# ICM.net
KiCad netlist of a schematic drawn in Altium Designer
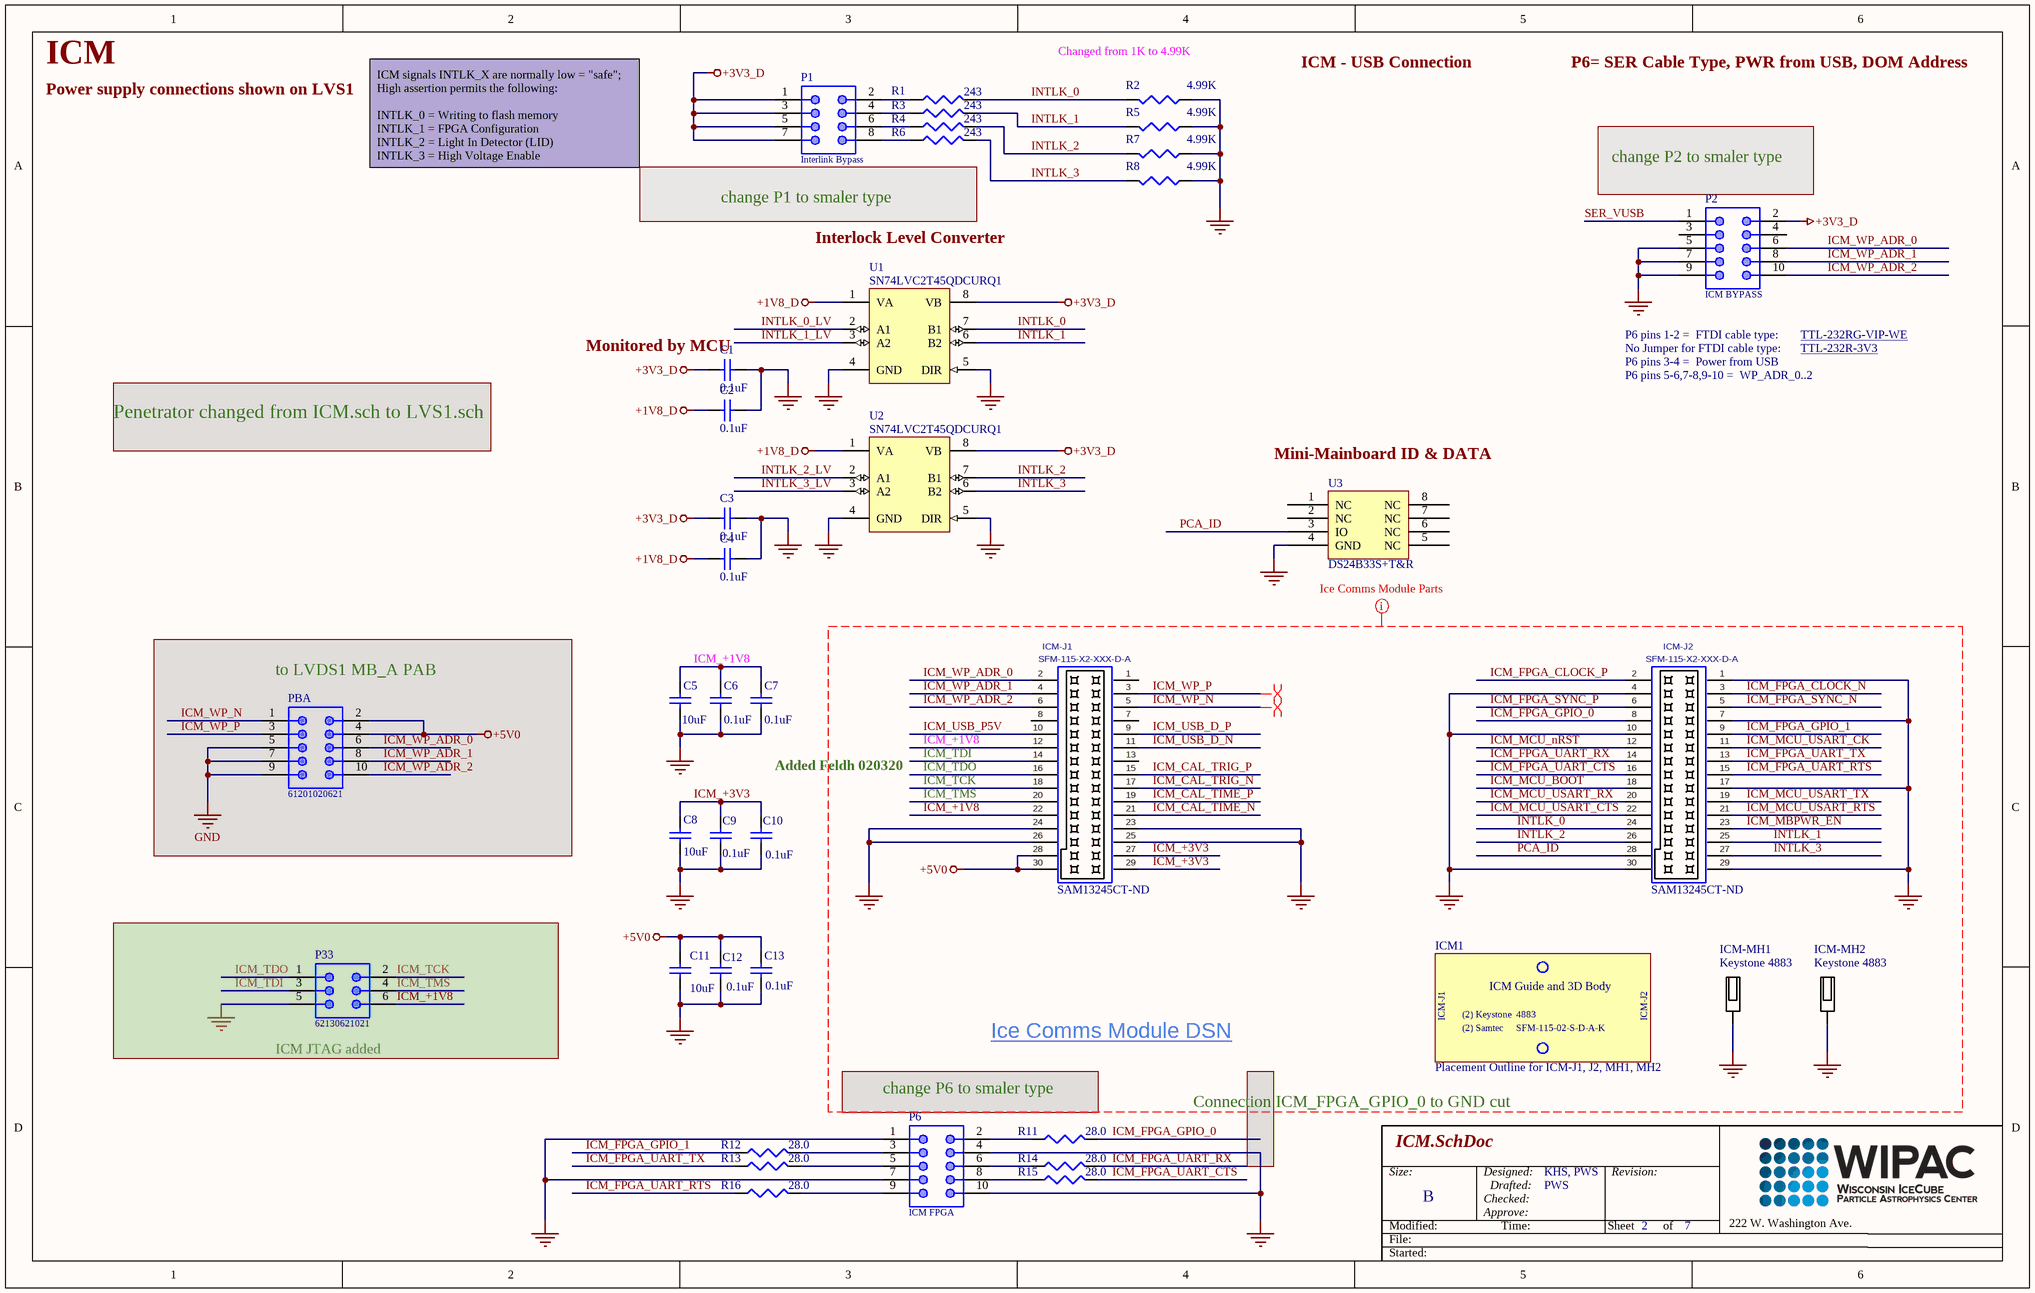
[diagram p0: ICM.SchDoc]

(export (version "E")
  (design (tool "Eeschema 10.0.6"))
  (components
    (comp (ref "C1")
      (value "0.1uF_603_50V")
      (footprint "CAPC_0603")
      (description "0.1µF ±10% 50V Ceramic Capacitor X7R 0603 (1608 Metric)")
      (fields
        (field (name "MANUFACTURER") "TDK")
        (field (name "MANUFACTURER PART NUMBER") "CGJ3E2X7R1H104K080AA")
        (field (name "CAPACITANCE") "0.1uF")
      )
      (libsource (lib "Custom1") (part "CapC_0.1uF_603_50V"))
    )
    (comp (ref "C2")
      (value "0.1uF_603_50V")
      (footprint "CAPC_0603")
      (description "0.1µF ±10% 50V Ceramic Capacitor X7R 0603 (1608 Metric)")
      (fields
        (field (name "MANUFACTURER") "TDK")
        (field (name "MANUFACTURER PART NUMBER") "CGJ3E2X7R1H104K080AA")
        (field (name "CAPACITANCE") "0.1uF")
      )
      (libsource (lib "Custom1") (part "CapC_0.1uF_603_50V"))
    )
    (comp (ref "C3")
      (value "0.1uF_603_50V")
      (footprint "CAPC_0603")
      (description "0.1µF ±10% 50V Ceramic Capacitor X7R 0603 (1608 Metric)")
      (fields
        (field (name "MANUFACTURER") "TDK")
        (field (name "MANUFACTURER PART NUMBER") "CGJ3E2X7R1H104K080AA")
        (field (name "CAPACITANCE") "0.1uF")
      )
      (libsource (lib "Custom1") (part "CapC_0.1uF_603_50V"))
    )
    (comp (ref "C4")
      (value "0.1uF_603_50V")
      (footprint "CAPC_0603")
      (description "0.1µF ±10% 50V Ceramic Capacitor X7R 0603 (1608 Metric)")
      (fields
        (field (name "MANUFACTURER") "TDK")
        (field (name "MANUFACTURER PART NUMBER") "CGJ3E2X7R1H104K080AA")
        (field (name "CAPACITANCE") "0.1uF")
      )
      (libsource (lib "Custom1") (part "CapC_0.1uF_603_50V"))
    )
    (comp (ref "C5")
      (value "10uF_805_10V")
      (footprint "CAPC_0805")
      (description "Capacitor")
      (fields
        (field (name "MANUFACTURER") "Murata")
        (field (name "MANUFACTURER PART NUMBER") "GCJ21BR71A106KE01L")
        (field (name "CAPACITANCE") "10uF")
      )
      (libsource (lib "Custom1") (part "CapC_10uF_805_10V"))
    )
    (comp (ref "C6")
      (value "0.1uF_603_50V")
      (footprint "CAPC_0603")
      (description "0.1µF ±10% 50V Ceramic Capacitor X7R 0603 (1608 Metric)")
      (fields
        (field (name "MANUFACTURER") "Murata")
        (field (name "MANUFACTURER PART NUMBER") "GCJ188R71H104KA12D")
        (field (name "CAPACITANCE") "0.1uF")
      )
      (libsource (lib "Custom1") (part "CapC_0.1uF_603_50V_GCJ"))
    )
    (comp (ref "C7")
      (value "0.1uF_603_50V")
      (footprint "CAPC_0603")
      (description "0.1µF ±10% 50V Ceramic Capacitor X7R 0603 (1608 Metric)")
      (fields
        (field (name "MANUFACTURER") "Murata")
        (field (name "MANUFACTURER PART NUMBER") "GCJ188R71H104KA12D")
        (field (name "CAPACITANCE") "0.1uF")
      )
      (libsource (lib "Custom1") (part "CapC_0.1uF_603_50V_GCJ"))
    )
    (comp (ref "C8")
      (value "10uF_805_10V")
      (footprint "CAPC_0805")
      (description "Capacitor")
      (fields
        (field (name "MANUFACTURER") "Murata")
        (field (name "MANUFACTURER PART NUMBER") "GCJ21BR71A106KE01L")
        (field (name "CAPACITANCE") "10uF")
      )
      (libsource (lib "Custom1") (part "CapC_10uF_805_10V"))
    )
    (comp (ref "C9")
      (value "0.1uF_603_50V")
      (footprint "CAPC_0603")
      (description "0.1µF ±10% 50V Ceramic Capacitor X7R 0603 (1608 Metric)")
      (fields
        (field (name "MANUFACTURER") "Murata")
        (field (name "MANUFACTURER PART NUMBER") "GCJ188R71H104KA12D")
        (field (name "CAPACITANCE") "0.1uF")
      )
      (libsource (lib "Custom1") (part "CapC_0.1uF_603_50V_GCJ"))
    )
    (comp (ref "C10")
      (value "0.1uF_603_50V")
      (footprint "CAPC_0603")
      (description "0.1µF ±10% 50V Ceramic Capacitor X7R 0603 (1608 Metric)")
      (fields
        (field (name "MANUFACTURER") "Murata")
        (field (name "MANUFACTURER PART NUMBER") "GCJ188R71H104KA12D")
        (field (name "CAPACITANCE") "0.1uF")
      )
      (libsource (lib "Custom1") (part "CapC_0.1uF_603_50V_GCJ"))
    )
    (comp (ref "C11")
      (value "10uF_805_10V")
      (footprint "CAPC_0805")
      (description "Capacitor")
      (fields
        (field (name "MANUFACTURER") "Murata")
        (field (name "MANUFACTURER PART NUMBER") "GCJ21BR71A106KE01L")
        (field (name "CAPACITANCE") "10uF")
      )
      (libsource (lib "Custom1") (part "CapC_10uF_805_10V"))
    )
    (comp (ref "C12")
      (value "0.1uF_603_50V")
      (footprint "CAPC_0603")
      (description "0.1µF ±10% 50V Ceramic Capacitor X7R 0603 (1608 Metric)")
      (fields
        (field (name "MANUFACTURER") "Murata")
        (field (name "MANUFACTURER PART NUMBER") "GCJ188R71H104KA12D")
        (field (name "CAPACITANCE") "0.1uF")
      )
      (libsource (lib "Custom1") (part "CapC_0.1uF_603_50V_GCJ"))
    )
    (comp (ref "C13")
      (value "0.1uF_603_50V")
      (footprint "CAPC_0603")
      (description "0.1µF ±10% 50V Ceramic Capacitor X7R 0603 (1608 Metric)")
      (fields
        (field (name "MANUFACTURER") "Murata")
        (field (name "MANUFACTURER PART NUMBER") "GCJ188R71H104KA12D")
        (field (name "CAPACITANCE") "0.1uF")
      )
      (libsource (lib "Custom1") (part "CapC_0.1uF_603_50V_GCJ"))
    )
    (comp (ref "ICM-J1")
      (value "SFM-115-X2-XXX-D-A")
      (footprint "SFM-115-X2-XXX-D-A")
      (description "SOCKET STRIP, .050\" (1.27mm) PITCH, SURFACE MOUNT.")
      (fields
        (field (name "MANUFACTURER") "Samtec")
        (field (name "MANUFACTURER PART NUMBER") "SFM-115-02-S-D-A-K-TR")
        (field (name "SUPPLIER PART NUMBER 1") "SAM13245CT-ND")
      )
      (libsource (lib "Custom1") (part "SFM-115-X2-XXX-D-A"))
    )
    (comp (ref "ICM-J2")
      (value "SFM-115-X2-XXX-D-A")
      (footprint "SFM-115-X2-XXX-D-A")
      (description "SOCKET STRIP, .050\" (1.27mm) PITCH, SURFACE MOUNT.")
      (fields
        (field (name "MANUFACTURER") "Samtec")
        (field (name "MANUFACTURER PART NUMBER") "SFM-115-02-S-D-A-K-TR")
        (field (name "SUPPLIER PART NUMBER 1") "SAM13245CT-ND")
      )
      (libsource (lib "Custom1") (part "SFM-115-X2-XXX-D-A"))
    )
    (comp (ref "ICM-MH1")
      (value "Keystone 4883")
      (footprint "Keystone 4883 solder")
      (description "standoff, SMT, 4-40, 0.25\" Long")
      (fields
        (field (name "MANUFACTURER") "Keystone Electronics")
        (field (name "MANUFACTURER PART NUMBER") "4883")
      )
      (libsource (lib "Custom1") (part "Keystone 4883"))
    )
    (comp (ref "ICM-MH2")
      (value "Keystone 4883")
      (footprint "Keystone 4883 solder")
      (description "standoff, SMT, 4-40, 0.25\" Long")
      (fields
        (field (name "MANUFACTURER") "Keystone Electronics")
        (field (name "MANUFACTURER PART NUMBER") "4883")
      )
      (libsource (lib "Custom1") (part "Keystone 4883"))
    )
    (comp (ref "ICM1")
      (value "Placement Outline for ICM-J1, J2, MH1, MH2")
      (footprint "Ice Comms Module")
      (libsource (lib "Custom1") (part "Ice Comms Module"))
    )
    (comp (ref "P1")
      (value "Interlink Bypass")
      (footprint "62100821021")
      (description "WR-PHD Pin Header, SMT, pitch 1.27mm, Dual Row, Vertical, 8pin")
      (fields (field (name "PART NUMBER") "62100821021") (field (name "PUBLISHER") "Wurth Elektronik"))
      (libsource (lib "WR-PHD") (part "62100821021"))
    )
    (comp (ref "P2")
      (value "ICM BYPASS")
      (footprint "62101021021")
      (description "WR-PHD Pin Header, SMT, pitch 1.27mm, Dual Row, Vertical, 10pin")
      (fields (field (name "PART NUMBER") "62101021021") (field (name "PUBLISHER") "Wurth Elektronik"))
      (libsource (lib "WR-PHD") (part "62101021021"))
    )
    (comp (ref "P6")
      (value "ICM FPGA")
      (footprint "62101021021")
      (description "WR-PHD Pin Header, SMT, pitch 1.27mm, Dual Row, Vertical, 10pin")
      (fields (field (name "PART NUMBER") "62101021021") (field (name "PUBLISHER") "Wurth Elektronik"))
      (libsource (lib "WR-PHD") (part "62101021021"))
    )
    (comp (ref "P33")
      (value "62130621021")
      (footprint "62130621021")
      (description "WR-PHD Pin Header, SMT, pitch 1.27mm, Dual Row, Vertical, 6pin")
      (fields (field (name "PUBLISHER") "Wurth Elektronik"))
      (libsource (lib "WR-PHD") (part "62130621021"))
    )
    (comp (ref "PBA")
      (value "61201020621")
      (footprint "61201020621")
      (description "Male Box Header WR-BHD, SMT, Vertical, pitch 2.54 mm, 10 pins")
      (fields (field (name "PUBLISHER") "Wurth Elektronik"))
      (libsource (lib "o162711v243 Altium_WR-BHD (rev19a)") (part "61201020621"))
    )
    (comp (ref "R1")
      (value "R_243_603_1%")
      (footprint "RES_0603")
      (description "RES 243 OHM 1/10W 1% 0603 SMD")
      (fields
        (field (name "MANUFACTURER") "Panasonic")
        (field (name "MANUFACTURER PART NUMBER") "ERJ3EKF2430V")
        (field (name "RESISTANCE") "243")
      )
      (libsource (lib "Custom1") (part "R_243_603_1%"))
    )
    (comp (ref "R2")
      (value "R_4.99K_603_1%")
      (footprint "RES_0603")
      (description "RES 4.99K OHM 1/10W 1% 0603 SMD")
      (fields
        (field (name "MANUFACTURER") "Panasonic")
        (field (name "MANUFACTURER PART NUMBER") "ERJ3EKF4991V")
        (field (name "RESISTANCE") "4.99K")
      )
      (libsource (lib "Custom1") (part "R_4.99K_603_1%"))
    )
    (comp (ref "R3")
      (value "R_243_603_1%")
      (footprint "RES_0603")
      (description "RES 243 OHM 1/10W 1% 0603 SMD")
      (fields
        (field (name "MANUFACTURER") "Panasonic")
        (field (name "MANUFACTURER PART NUMBER") "ERJ3EKF2430V")
        (field (name "RESISTANCE") "243")
      )
      (libsource (lib "Custom1") (part "R_243_603_1%"))
    )
    (comp (ref "R4")
      (value "R_243_603_1%")
      (footprint "RES_0603")
      (description "RES 243 OHM 1/10W 1% 0603 SMD")
      (fields
        (field (name "MANUFACTURER") "Panasonic")
        (field (name "MANUFACTURER PART NUMBER") "ERJ3EKF2430V")
        (field (name "RESISTANCE") "243")
      )
      (libsource (lib "Custom1") (part "R_243_603_1%"))
    )
    (comp (ref "R5")
      (value "R_4.99K_603_1%")
      (footprint "RES_0603")
      (description "RES 4.99K OHM 1/10W 1% 0603 SMD")
      (fields
        (field (name "MANUFACTURER") "Panasonic")
        (field (name "MANUFACTURER PART NUMBER") "ERJ3EKF4991V")
        (field (name "RESISTANCE") "4.99K")
      )
      (libsource (lib "Custom1") (part "R_4.99K_603_1%"))
    )
    (comp (ref "R6")
      (value "R_243_603_1%")
      (footprint "RES_0603")
      (description "RES 243 OHM 1/10W 1% 0603 SMD")
      (fields
        (field (name "MANUFACTURER") "Panasonic")
        (field (name "MANUFACTURER PART NUMBER") "ERJ3EKF2430V")
        (field (name "RESISTANCE") "243")
      )
      (libsource (lib "Custom1") (part "R_243_603_1%"))
    )
    (comp (ref "R7")
      (value "R_4.99K_603_1%")
      (footprint "RES_0603")
      (description "RES 4.99K OHM 1/10W 1% 0603 SMD")
      (fields
        (field (name "MANUFACTURER") "Panasonic")
        (field (name "MANUFACTURER PART NUMBER") "ERJ3EKF4991V")
        (field (name "RESISTANCE") "4.99K")
      )
      (libsource (lib "Custom1") (part "R_4.99K_603_1%"))
    )
    (comp (ref "R8")
      (value "R_4.99K_603_1%")
      (footprint "RES_0603")
      (description "RES 4.99K OHM 1/10W 1% 0603 SMD")
      (fields
        (field (name "MANUFACTURER") "Panasonic")
        (field (name "MANUFACTURER PART NUMBER") "ERJ3EKF4991V")
        (field (name "RESISTANCE") "4.99K")
      )
      (libsource (lib "Custom1") (part "R_4.99K_603_1%"))
    )
    (comp (ref "R11")
      (value "R_28.0_603_1%")
      (footprint "RES_0603")
      (description "RES 28.0 OHM 1/10W 1% 0603 SMD")
      (fields
        (field (name "MANUFACTURER") "Panasonic")
        (field (name "MANUFACTURER PART NUMBER") "ERJ3EKF28R0V")
        (field (name "RESISTANCE") "28.0")
      )
      (libsource (lib "Custom1") (part "R_28.0_603_1%"))
    )
    (comp (ref "R12")
      (value "R_28.0_603_1%")
      (footprint "RES_0603")
      (description "RES 28.0 OHM 1/10W 1% 0603 SMD")
      (fields
        (field (name "MANUFACTURER") "Panasonic")
        (field (name "MANUFACTURER PART NUMBER") "ERJ3EKF28R0V")
        (field (name "RESISTANCE") "28.0")
      )
      (libsource (lib "Custom1") (part "R_28.0_603_1%"))
    )
    (comp (ref "R13")
      (value "R_28.0_603_1%")
      (footprint "RES_0603")
      (description "RES 28.0 OHM 1/10W 1% 0603 SMD")
      (fields
        (field (name "MANUFACTURER") "Panasonic")
        (field (name "MANUFACTURER PART NUMBER") "ERJ3EKF28R0V")
        (field (name "RESISTANCE") "28.0")
      )
      (libsource (lib "Custom1") (part "R_28.0_603_1%"))
    )
    (comp (ref "R14")
      (value "R_28.0_603_1%")
      (footprint "RES_0603")
      (description "RES 28.0 OHM 1/10W 1% 0603 SMD")
      (fields
        (field (name "MANUFACTURER") "Panasonic")
        (field (name "MANUFACTURER PART NUMBER") "ERJ3EKF28R0V")
        (field (name "RESISTANCE") "28.0")
      )
      (libsource (lib "Custom1") (part "R_28.0_603_1%"))
    )
    (comp (ref "R15")
      (value "R_28.0_603_1%")
      (footprint "RES_0603")
      (description "RES 28.0 OHM 1/10W 1% 0603 SMD")
      (fields
        (field (name "MANUFACTURER") "Panasonic")
        (field (name "MANUFACTURER PART NUMBER") "ERJ3EKF28R0V")
        (field (name "RESISTANCE") "28.0")
      )
      (libsource (lib "Custom1") (part "R_28.0_603_1%"))
    )
    (comp (ref "R16")
      (value "R_28.0_603_1%")
      (footprint "RES_0603")
      (description "RES 28.0 OHM 1/10W 1% 0603 SMD")
      (fields
        (field (name "MANUFACTURER") "Panasonic")
        (field (name "MANUFACTURER PART NUMBER") "ERJ3EKF28R0V")
        (field (name "RESISTANCE") "28.0")
      )
      (libsource (lib "Custom1") (part "R_28.0_603_1%"))
    )
    (comp (ref "U1")
      (value "SN74LVC2T45QDCURQ1")
      (footprint "TI-DGK8_N")
      (description "Voltage Level Translator Bidirectional 1 Circuit 2 Channel 420Mbps SM8 (SSOP)")
      (fields
        (field (name "GENERIC PART NUMBER") "SN74LVC2T45-Q1")
        (field (name "MANUFACTURER") "Texas Instruments")
      )
      (libsource (lib "Custom1") (part "SN74LVC2T45QDCURQ1"))
    )
    (comp (ref "U2")
      (value "SN74LVC2T45QDCURQ1")
      (footprint "TI-DGK8_N")
      (description "Voltage Level Translator Bidirectional 1 Circuit 2 Channel 420Mbps SM8 (SSOP)")
      (fields
        (field (name "GENERIC PART NUMBER") "SN74LVC2T45-Q1")
        (field (name "MANUFACTURER") "Texas Instruments")
      )
      (libsource (lib "Custom1") (part "SN74LVC2T45QDCURQ1"))
    )
    (comp (ref "U3")
      (value "DS24B33S+T&R")
      (footprint "W8+2_M")
      (description "EEPROM Memory IC 4Kb (256 x 16) 1-Wire®  2µs 8-SO")
      (fields (field (name "MANUFACTURER") "Maxim"))
      (libsource (lib "Custom1") (part "DS24B33S+T&R"))
    )
  )
  (nets
    (net (code "1") (name "+1V8_D") (class "Default")
      (node (ref "C2") (pin "2") (pinfunction "2_2") (pintype "passive"))
      (node (ref "C4") (pin "2") (pinfunction "2_2") (pintype "passive"))
      (node (ref "U1") (pin "1") (pinfunction "VA_1") (pintype "power_in"))
      (node (ref "U2") (pin "1") (pinfunction "VA_1") (pintype "power_in"))
    )
    (net (code "2") (name "+3V3_D") (class "Default")
      (node (ref "C1") (pin "2") (pinfunction "2_2") (pintype "passive"))
      (node (ref "C3") (pin "2") (pinfunction "2_2") (pintype "passive"))
      (node (ref "P1") (pin "1") (pinfunction "1_1") (pintype "passive"))
      (node (ref "P1") (pin "3") (pinfunction "3_3") (pintype "passive"))
      (node (ref "P1") (pin "5") (pinfunction "5_5") (pintype "passive"))
      (node (ref "P1") (pin "7") (pinfunction "7_7") (pintype "passive"))
      (node (ref "P2") (pin "2") (pinfunction "2_2") (pintype "passive"))
      (node (ref "U1") (pin "8") (pinfunction "VB_8") (pintype "power_in"))
      (node (ref "U2") (pin "8") (pinfunction "VB_8") (pintype "power_in"))
    )
    (net (code "3") (name "+5V0") (class "Default")
      (node (ref "C11") (pin "2") (pinfunction "2_2") (pintype "passive"))
      (node (ref "C12") (pin "2") (pinfunction "2_2") (pintype "passive"))
      (node (ref "C13") (pin "2") (pinfunction "2_2") (pintype "passive"))
      (node (ref "ICM-J1") (pin "28") (pinfunction "28_28") (pintype "passive"))
      (node (ref "ICM-J1") (pin "30") (pinfunction "30_30") (pintype "passive"))
      (node (ref "PBA") (pin "2") (pinfunction "2_2") (pintype "passive"))
      (node (ref "PBA") (pin "4") (pinfunction "4_4") (pintype "passive"))
    )
    (net (code "4") (name "/ICM_+1V8") (class "Default")
      (node (ref "C5") (pin "2") (pinfunction "2_2") (pintype "passive"))
      (node (ref "C6") (pin "2") (pinfunction "2_2") (pintype "passive"))
      (node (ref "C7") (pin "2") (pinfunction "2_2") (pintype "passive"))
      (node (ref "ICM-J1") (pin "12") (pinfunction "12_12") (pintype "passive"))
      (node (ref "ICM-J1") (pin "22") (pinfunction "22_22") (pintype "passive"))
      (node (ref "P33") (pin "6") (pinfunction "6_6") (pintype "passive"))
    )
    (net (code "5") (name "/ICM_+3V3") (class "Default")
      (node (ref "C10") (pin "2") (pinfunction "2_2") (pintype "passive"))
      (node (ref "C8") (pin "2") (pinfunction "2_2") (pintype "passive"))
      (node (ref "C9") (pin "2") (pinfunction "2_2") (pintype "passive"))
      (node (ref "ICM-J1") (pin "27") (pinfunction "27_27") (pintype "passive"))
      (node (ref "ICM-J1") (pin "29") (pinfunction "29_29") (pintype "passive"))
    )
    (net (code "6") (name "/ICM_CAL_TIME_N") (class "Default")
      (node (ref "ICM-J1") (pin "21") (pinfunction "21_21") (pintype "passive"))
    )
    (net (code "7") (name "/ICM_CAL_TIME_P") (class "Default")
      (node (ref "ICM-J1") (pin "19") (pinfunction "19_19") (pintype "passive"))
    )
    (net (code "8") (name "/ICM_CAL_TRIG_N") (class "Default")
      (node (ref "ICM-J1") (pin "17") (pinfunction "17_17") (pintype "passive"))
    )
    (net (code "9") (name "/ICM_CAL_TRIG_P") (class "Default")
      (node (ref "ICM-J1") (pin "15") (pinfunction "15_15") (pintype "passive"))
    )
    (net (code "10") (name "/ICM_FPGA_CLOCK_N") (class "Default")
      (node (ref "ICM-J2") (pin "3") (pinfunction "3_3") (pintype "passive"))
    )
    (net (code "11") (name "/ICM_FPGA_CLOCK_P") (class "Default")
      (node (ref "ICM-J2") (pin "2") (pinfunction "2_2") (pintype "passive"))
    )
    (net (code "12") (name "/ICM_FPGA_GPIO_0") (class "Default")
      (node (ref "ICM-J2") (pin "8") (pinfunction "8_8") (pintype "passive"))
      (node (ref "R11") (pin "2") (pinfunction "2_2") (pintype "passive"))
    )
    (net (code "13") (name "/ICM_FPGA_GPIO_1") (class "Default")
      (node (ref "ICM-J2") (pin "9") (pinfunction "9_9") (pintype "passive"))
      (node (ref "R12") (pin "1") (pinfunction "1_1") (pintype "passive"))
    )
    (net (code "14") (name "/ICM_FPGA_SYNC_N") (class "Default")
      (node (ref "ICM-J2") (pin "5") (pinfunction "5_5") (pintype "passive"))
    )
    (net (code "15") (name "/ICM_FPGA_SYNC_P") (class "Default")
      (node (ref "ICM-J2") (pin "6") (pinfunction "6_6") (pintype "passive"))
    )
    (net (code "16") (name "/ICM_FPGA_UART_CTS") (class "Default")
      (node (ref "ICM-J2") (pin "16") (pinfunction "16_16") (pintype "passive"))
      (node (ref "R15") (pin "2") (pinfunction "2_2") (pintype "passive"))
    )
    (net (code "17") (name "/ICM_FPGA_UART_RTS") (class "Default")
      (node (ref "ICM-J2") (pin "15") (pinfunction "15_15") (pintype "passive"))
      (node (ref "R16") (pin "1") (pinfunction "1_1") (pintype "passive"))
    )
    (net (code "18") (name "/ICM_FPGA_UART_RX") (class "Default")
      (node (ref "ICM-J2") (pin "14") (pinfunction "14_14") (pintype "passive"))
      (node (ref "R14") (pin "2") (pinfunction "2_2") (pintype "passive"))
    )
    (net (code "19") (name "/ICM_FPGA_UART_TX") (class "Default")
      (node (ref "ICM-J2") (pin "13") (pinfunction "13_13") (pintype "passive"))
      (node (ref "R13") (pin "1") (pinfunction "1_1") (pintype "passive"))
    )
    (net (code "20") (name "/ICM_MBPWR_EN") (class "Default")
      (node (ref "ICM-J2") (pin "23") (pinfunction "23_23") (pintype "passive"))
    )
    (net (code "21") (name "/ICM_MCU_BOOT") (class "Default")
      (node (ref "ICM-J2") (pin "18") (pinfunction "18_18") (pintype "passive"))
    )
    (net (code "22") (name "/ICM_MCU_USART_CK") (class "Default")
      (node (ref "ICM-J2") (pin "11") (pinfunction "11_11") (pintype "passive"))
    )
    (net (code "23") (name "/ICM_MCU_USART_CTS") (class "Default")
      (node (ref "ICM-J2") (pin "22") (pinfunction "22_22") (pintype "passive"))
    )
    (net (code "24") (name "/ICM_MCU_USART_RTS") (class "Default")
      (node (ref "ICM-J2") (pin "21") (pinfunction "21_21") (pintype "passive"))
    )
    (net (code "25") (name "/ICM_MCU_USART_RX") (class "Default")
      (node (ref "ICM-J2") (pin "20") (pinfunction "20_20") (pintype "passive"))
    )
    (net (code "26") (name "/ICM_MCU_USART_TX") (class "Default")
      (node (ref "ICM-J2") (pin "19") (pinfunction "19_19") (pintype "passive"))
    )
    (net (code "27") (name "/ICM_MCU_nRST") (class "Default")
      (node (ref "ICM-J2") (pin "12") (pinfunction "12_12") (pintype "passive"))
    )
    (net (code "28") (name "/ICM_TCK") (class "Default")
      (node (ref "ICM-J1") (pin "18") (pinfunction "18_18") (pintype "passive"))
      (node (ref "P33") (pin "2") (pinfunction "2_2") (pintype "passive"))
    )
    (net (code "29") (name "/ICM_TDI") (class "Default")
      (node (ref "ICM-J1") (pin "14") (pinfunction "14_14") (pintype "passive"))
      (node (ref "P33") (pin "3") (pinfunction "3_3") (pintype "passive"))
    )
    (net (code "30") (name "/ICM_TDO") (class "Default")
      (node (ref "ICM-J1") (pin "16") (pinfunction "16_16") (pintype "passive"))
      (node (ref "P33") (pin "1") (pinfunction "1_1") (pintype "passive"))
    )
    (net (code "31") (name "/ICM_TMS") (class "Default")
      (node (ref "ICM-J1") (pin "20") (pinfunction "20_20") (pintype "passive"))
      (node (ref "P33") (pin "4") (pinfunction "4_4") (pintype "passive"))
    )
    (net (code "32") (name "/ICM_USB_D_N") (class "Default")
      (node (ref "ICM-J1") (pin "11") (pinfunction "11_11") (pintype "passive"))
    )
    (net (code "33") (name "/ICM_USB_D_P") (class "Default")
      (node (ref "ICM-J1") (pin "9") (pinfunction "9_9") (pintype "passive"))
    )
    (net (code "34") (name "/ICM_USB_P5V") (class "Default")
      (node (ref "ICM-J1") (pin "10") (pinfunction "10_10") (pintype "passive"))
    )
    (net (code "35") (name "/ICM_WP_ADR_0") (class "Default")
      (node (ref "ICM-J1") (pin "2") (pinfunction "2_2") (pintype "passive"))
      (node (ref "P2") (pin "6") (pinfunction "6_6") (pintype "passive"))
      (node (ref "PBA") (pin "6") (pinfunction "6_6") (pintype "passive"))
    )
    (net (code "36") (name "/ICM_WP_ADR_1") (class "Default")
      (node (ref "ICM-J1") (pin "4") (pinfunction "4_4") (pintype "passive"))
      (node (ref "P2") (pin "8") (pinfunction "8_8") (pintype "passive"))
      (node (ref "PBA") (pin "8") (pinfunction "8_8") (pintype "passive"))
    )
    (net (code "37") (name "/ICM_WP_ADR_2") (class "Default")
      (node (ref "ICM-J1") (pin "6") (pinfunction "6_6") (pintype "passive"))
      (node (ref "P2") (pin "10") (pinfunction "10_10") (pintype "passive"))
      (node (ref "PBA") (pin "10") (pinfunction "10_10") (pintype "passive"))
    )
    (net (code "38") (name "/ICM_WP_N") (class "Default")
      (node (ref "ICM-J1") (pin "5") (pinfunction "5_5") (pintype "passive"))
      (node (ref "PBA") (pin "1") (pinfunction "1_1") (pintype "passive"))
    )
    (net (code "39") (name "/ICM_WP_P") (class "Default")
      (node (ref "ICM-J1") (pin "3") (pinfunction "3_3") (pintype "passive"))
      (node (ref "PBA") (pin "3") (pinfunction "3_3") (pintype "passive"))
    )
    (net (code "40") (name "/INTLK_0") (class "Default")
      (node (ref "ICM-J2") (pin "24") (pinfunction "24_24") (pintype "passive"))
      (node (ref "R1") (pin "2") (pinfunction "2_2") (pintype "passive"))
      (node (ref "R2") (pin "2") (pinfunction "2_2") (pintype "passive"))
      (node (ref "U1") (pin "7") (pinfunction "B1_7") (pintype "bidirectional"))
    )
    (net (code "41") (name "/INTLK_0_LV") (class "Default")
      (node (ref "U1") (pin "2") (pinfunction "A1_2") (pintype "bidirectional"))
    )
    (net (code "42") (name "/INTLK_1") (class "Default")
      (node (ref "ICM-J2") (pin "25") (pinfunction "25_25") (pintype "passive"))
      (node (ref "R3") (pin "2") (pinfunction "2_2") (pintype "passive"))
      (node (ref "R5") (pin "2") (pinfunction "2_2") (pintype "passive"))
      (node (ref "U1") (pin "6") (pinfunction "B2_6") (pintype "bidirectional"))
    )
    (net (code "43") (name "/INTLK_1_LV") (class "Default")
      (node (ref "U1") (pin "3") (pinfunction "A2_3") (pintype "bidirectional"))
    )
    (net (code "44") (name "/INTLK_2") (class "Default")
      (node (ref "ICM-J2") (pin "26") (pinfunction "26_26") (pintype "passive"))
      (node (ref "R4") (pin "2") (pinfunction "2_2") (pintype "passive"))
      (node (ref "R7") (pin "2") (pinfunction "2_2") (pintype "passive"))
      (node (ref "U2") (pin "7") (pinfunction "B1_7") (pintype "bidirectional"))
    )
    (net (code "45") (name "/INTLK_2_LV") (class "Default")
      (node (ref "U2") (pin "2") (pinfunction "A1_2") (pintype "bidirectional"))
    )
    (net (code "46") (name "/INTLK_3") (class "Default")
      (node (ref "ICM-J2") (pin "27") (pinfunction "27_27") (pintype "passive"))
      (node (ref "R6") (pin "2") (pinfunction "2_2") (pintype "passive"))
      (node (ref "R8") (pin "2") (pinfunction "2_2") (pintype "passive"))
      (node (ref "U2") (pin "6") (pinfunction "B2_6") (pintype "bidirectional"))
    )
    (net (code "47") (name "/INTLK_3_LV") (class "Default")
      (node (ref "U2") (pin "3") (pinfunction "A2_3") (pintype "bidirectional"))
    )
    (net (code "48") (name "/PCA_ID") (class "Default")
      (node (ref "ICM-J2") (pin "28") (pinfunction "28_28") (pintype "passive"))
      (node (ref "U3") (pin "3") (pinfunction "IO_3") (pintype "passive"))
    )
    (net (code "49") (name "/SER_VUSB") (class "Default")
      (node (ref "P2") (pin "1") (pinfunction "1_1") (pintype "passive"))
    )
    (net (code "50") (name "GND") (class "Default")
      (node (ref "C1") (pin "1") (pinfunction "1_1") (pintype "passive"))
      (node (ref "C10") (pin "1") (pinfunction "1_1") (pintype "passive"))
      (node (ref "C11") (pin "1") (pinfunction "1_1") (pintype "passive"))
      (node (ref "C12") (pin "1") (pinfunction "1_1") (pintype "passive"))
      (node (ref "C13") (pin "1") (pinfunction "1_1") (pintype "passive"))
      (node (ref "C2") (pin "1") (pinfunction "1_1") (pintype "passive"))
      (node (ref "C3") (pin "1") (pinfunction "1_1") (pintype "passive"))
      (node (ref "C4") (pin "1") (pinfunction "1_1") (pintype "passive"))
      (node (ref "C5") (pin "1") (pinfunction "1_1") (pintype "passive"))
      (node (ref "C6") (pin "1") (pinfunction "1_1") (pintype "passive"))
      (node (ref "C7") (pin "1") (pinfunction "1_1") (pintype "passive"))
      (node (ref "C8") (pin "1") (pinfunction "1_1") (pintype "passive"))
      (node (ref "C9") (pin "1") (pinfunction "1_1") (pintype "passive"))
      (node (ref "ICM-J1") (pin "23") (pinfunction "23_23") (pintype "passive"))
      (node (ref "ICM-J1") (pin "24") (pinfunction "24_24") (pintype "passive"))
      (node (ref "ICM-J1") (pin "25") (pinfunction "25_25") (pintype "passive"))
      (node (ref "ICM-J1") (pin "26") (pinfunction "26_26") (pintype "passive"))
      (node (ref "ICM-J2") (pin "1") (pinfunction "1_1") (pintype "passive"))
      (node (ref "ICM-J2") (pin "10") (pinfunction "10_10") (pintype "passive"))
      (node (ref "ICM-J2") (pin "17") (pinfunction "17_17") (pintype "passive"))
      (node (ref "ICM-J2") (pin "29") (pinfunction "29_29") (pintype "passive"))
      (node (ref "ICM-J2") (pin "30") (pinfunction "30_30") (pintype "passive"))
      (node (ref "ICM-J2") (pin "4") (pinfunction "4_4") (pintype "passive"))
      (node (ref "ICM-J2") (pin "7") (pinfunction "7_7") (pintype "passive"))
      (node (ref "ICM-MH1") (pin "1") (pinfunction "Standoff_1") (pintype "passive"))
      (node (ref "ICM-MH2") (pin "1") (pinfunction "Standoff_1") (pintype "passive"))
      (node (ref "P2") (pin "5") (pinfunction "5_5") (pintype "passive"))
      (node (ref "P2") (pin "7") (pinfunction "7_7") (pintype "passive"))
      (node (ref "P2") (pin "9") (pinfunction "9_9") (pintype "passive"))
      (node (ref "P33") (pin "5") (pinfunction "5_5") (pintype "passive"))
      (node (ref "P6") (pin "1") (pinfunction "1_1") (pintype "passive"))
      (node (ref "P6") (pin "10") (pinfunction "10_10") (pintype "passive"))
      (node (ref "P6") (pin "4") (pinfunction "4_4") (pintype "passive"))
      (node (ref "P6") (pin "7") (pinfunction "7_7") (pintype "passive"))
      (node (ref "PBA") (pin "5") (pinfunction "5_5") (pintype "passive"))
      (node (ref "PBA") (pin "7") (pinfunction "7_7") (pintype "passive"))
      (node (ref "PBA") (pin "9") (pinfunction "9_9") (pintype "passive"))
      (node (ref "R2") (pin "1") (pinfunction "1_1") (pintype "passive"))
      (node (ref "R5") (pin "1") (pinfunction "1_1") (pintype "passive"))
      (node (ref "R7") (pin "1") (pinfunction "1_1") (pintype "passive"))
      (node (ref "R8") (pin "1") (pinfunction "1_1") (pintype "passive"))
      (node (ref "U1") (pin "4") (pinfunction "GND_4") (pintype "power_in"))
      (node (ref "U1") (pin "5") (pinfunction "DIR_5") (pintype "input"))
      (node (ref "U2") (pin "4") (pinfunction "GND_4") (pintype "power_in"))
      (node (ref "U2") (pin "5") (pinfunction "DIR_5") (pintype "input"))
      (node (ref "U3") (pin "4") (pinfunction "GND_4") (pintype "passive"))
    )
    (net (code "51") (name "Net-(P1-Pad2)") (class "Default")
      (node (ref "P1") (pin "2") (pinfunction "2_2") (pintype "passive"))
      (node (ref "R1") (pin "1") (pinfunction "1_1") (pintype "passive"))
    )
    (net (code "52") (name "Net-(P1-Pad4)") (class "Default")
      (node (ref "P1") (pin "4") (pinfunction "4_4") (pintype "passive"))
      (node (ref "R3") (pin "1") (pinfunction "1_1") (pintype "passive"))
    )
    (net (code "53") (name "Net-(P1-Pad6)") (class "Default")
      (node (ref "P1") (pin "6") (pinfunction "6_6") (pintype "passive"))
      (node (ref "R4") (pin "1") (pinfunction "1_1") (pintype "passive"))
    )
    (net (code "54") (name "Net-(P1-Pad8)") (class "Default")
      (node (ref "P1") (pin "8") (pinfunction "8_8") (pintype "passive"))
      (node (ref "R6") (pin "1") (pinfunction "1_1") (pintype "passive"))
    )
    (net (code "55") (name "Net-(P6-Pad2)") (class "Default")
      (node (ref "P6") (pin "2") (pinfunction "2_2") (pintype "passive"))
      (node (ref "R11") (pin "1") (pinfunction "1_1") (pintype "passive"))
    )
    (net (code "56") (name "Net-(P6-Pad3)") (class "Default")
      (node (ref "P6") (pin "3") (pinfunction "3_3") (pintype "passive"))
      (node (ref "R12") (pin "2") (pinfunction "2_2") (pintype "passive"))
    )
    (net (code "57") (name "Net-(P6-Pad5)") (class "Default")
      (node (ref "P6") (pin "5") (pinfunction "5_5") (pintype "passive"))
      (node (ref "R13") (pin "2") (pinfunction "2_2") (pintype "passive"))
    )
    (net (code "58") (name "Net-(P6-Pad6)") (class "Default")
      (node (ref "P6") (pin "6") (pinfunction "6_6") (pintype "passive"))
      (node (ref "R14") (pin "1") (pinfunction "1_1") (pintype "passive"))
    )
    (net (code "59") (name "Net-(P6-Pad8)") (class "Default")
      (node (ref "P6") (pin "8") (pinfunction "8_8") (pintype "passive"))
      (node (ref "R15") (pin "1") (pinfunction "1_1") (pintype "passive"))
    )
    (net (code "60") (name "Net-(P6-Pad9)") (class "Default")
      (node (ref "P6") (pin "9") (pinfunction "9_9") (pintype "passive"))
      (node (ref "R16") (pin "2") (pinfunction "2_2") (pintype "passive"))
    )
    (net (code "61") (name "unconnected-(ICM-J1-Pad1)") (class "Default")
      (node (ref "ICM-J1") (pin "1") (pinfunction "1_1") (pintype "passive"))
    )
    (net (code "62") (name "unconnected-(ICM-J1-Pad7)") (class "Default")
      (node (ref "ICM-J1") (pin "7") (pinfunction "7_7") (pintype "passive"))
    )
    (net (code "63") (name "unconnected-(ICM-J1-Pad8)") (class "Default")
      (node (ref "ICM-J1") (pin "8") (pinfunction "8_8") (pintype "passive"))
    )
    (net (code "64") (name "unconnected-(ICM-J1-Pad13)") (class "Default")
      (node (ref "ICM-J1") (pin "13") (pinfunction "13_13") (pintype "passive"))
    )
    (net (code "65") (name "unconnected-(P2-Pad3)") (class "Default")
      (node (ref "P2") (pin "3") (pinfunction "3_3") (pintype "passive"))
    )
    (net (code "66") (name "unconnected-(P2-Pad4)") (class "Default")
      (node (ref "P2") (pin "4") (pinfunction "4_4") (pintype "passive"))
    )
    (net (code "67") (name "unconnected-(U3-NC-Pad1)") (class "Default")
      (node (ref "U3") (pin "1") (pinfunction "NC_1") (pintype "passive"))
    )
    (net (code "68") (name "unconnected-(U3-NC-Pad2)") (class "Default")
      (node (ref "U3") (pin "2") (pinfunction "NC_2") (pintype "passive"))
    )
    (net (code "69") (name "unconnected-(U3-NC-Pad5)") (class "Default")
      (node (ref "U3") (pin "5") (pinfunction "NC_5") (pintype "passive"))
    )
    (net (code "70") (name "unconnected-(U3-NC-Pad6)") (class "Default")
      (node (ref "U3") (pin "6") (pinfunction "NC_6") (pintype "passive"))
    )
    (net (code "71") (name "unconnected-(U3-NC-Pad7)") (class "Default")
      (node (ref "U3") (pin "7") (pinfunction "NC_7") (pintype "passive"))
    )
    (net (code "72") (name "unconnected-(U3-NC-Pad8)") (class "Default")
      (node (ref "U3") (pin "8") (pinfunction "NC_8") (pintype "passive"))
    )
  )
)
